# power_inputs.net
KiCad netlist of a schematic drawn in EAGLE
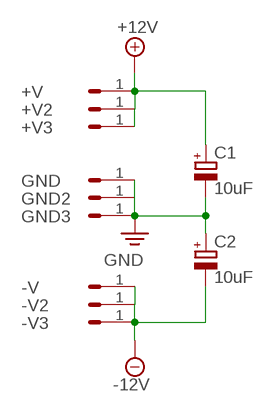
[diagram p0: schematic, sheet 1]

(export (version "E")
  (design (tool "Eeschema 10.0.6"))
  (components
    (comp (ref "+V")
      (value "HEADER/MALE/01")
      (footprint "eagle-import:HEADER_MALE_01")
      (fields (field (name "SPICEPREFIX") "X"))
      (libsource (lib "eagle-import") (part "HEADER/MALE/01"))
    )
    (comp (ref "+V2")
      (value "HEADER/MALE/01")
      (footprint "eagle-import:HEADER_MALE_01")
      (fields (field (name "SPICEPREFIX") "X"))
      (libsource (lib "eagle-import") (part "HEADER/MALE/01"))
    )
    (comp (ref "+V3")
      (value "HEADER/MALE/01")
      (footprint "eagle-import:HEADER_MALE_01")
      (fields (field (name "SPICEPREFIX") "X"))
      (libsource (lib "eagle-import") (part "HEADER/MALE/01"))
    )
    (comp (ref "-V")
      (value "HEADER/MALE/01")
      (footprint "eagle-import:HEADER_MALE_01")
      (fields (field (name "SPICEPREFIX") "X"))
      (libsource (lib "eagle-import") (part "HEADER/MALE/01"))
    )
    (comp (ref "-V2")
      (value "HEADER/MALE/01")
      (footprint "eagle-import:HEADER_MALE_01")
      (fields (field (name "SPICEPREFIX") "X"))
      (libsource (lib "eagle-import") (part "HEADER/MALE/01"))
    )
    (comp (ref "-V3")
      (value "HEADER/MALE/01")
      (footprint "eagle-import:HEADER_MALE_01")
      (fields (field (name "SPICEPREFIX") "X"))
      (libsource (lib "eagle-import") (part "HEADER/MALE/01"))
    )
    (comp (ref "C1")
      (value "10uF")
      (footprint "eagle-import:E2,5-6")
      (fields (field (name "SPICEPREFIX") "C"))
      (libsource (lib "eagle-import") (part "CAPACITOR/POLARIZEDE2.5-6"))
    )
    (comp (ref "C2")
      (value "10uF")
      (footprint "eagle-import:E2,5-6")
      (fields (field (name "SPICEPREFIX") "C"))
      (libsource (lib "eagle-import") (part "CAPACITOR/POLARIZEDE2.5-6"))
    )
    (comp (ref "GND")
      (value "HEADER/MALE/01")
      (footprint "eagle-import:HEADER_MALE_01")
      (fields (field (name "SPICEPREFIX") "X"))
      (libsource (lib "eagle-import") (part "HEADER/MALE/01"))
    )
    (comp (ref "GND2")
      (value "HEADER/MALE/01")
      (footprint "eagle-import:HEADER_MALE_01")
      (fields (field (name "SPICEPREFIX") "X"))
      (libsource (lib "eagle-import") (part "HEADER/MALE/01"))
    )
    (comp (ref "GND3")
      (value "HEADER/MALE/01")
      (footprint "eagle-import:HEADER_MALE_01")
      (fields (field (name "SPICEPREFIX") "X"))
      (libsource (lib "eagle-import") (part "HEADER/MALE/01"))
    )
  )
  (nets
    (net (code "1") (name "+12V") (class "Default")
      (node (ref "+V") (pin "1") (pinfunction "3_1") (pintype "passive"))
      (node (ref "+V2") (pin "1") (pinfunction "3_1") (pintype "passive"))
      (node (ref "+V3") (pin "1") (pinfunction "3_1") (pintype "passive"))
      (node (ref "C1") (pin "+") (pinfunction "+_+") (pintype "passive"))
    )
    (net (code "2") (name "-12V") (class "Default")
      (node (ref "-V") (pin "1") (pinfunction "3_1") (pintype "passive"))
      (node (ref "-V2") (pin "1") (pinfunction "3_1") (pintype "passive"))
      (node (ref "-V3") (pin "1") (pinfunction "3_1") (pintype "passive"))
      (node (ref "C2") (pin "-") (pinfunction "-_-") (pintype "passive"))
    )
    (net (code "3") (name "GND") (class "Default")
      (node (ref "C1") (pin "-") (pinfunction "-_-") (pintype "passive"))
      (node (ref "C2") (pin "+") (pinfunction "+_+") (pintype "passive"))
      (node (ref "GND") (pin "1") (pinfunction "3_1") (pintype "passive"))
      (node (ref "GND2") (pin "1") (pinfunction "3_1") (pintype "passive"))
      (node (ref "GND3") (pin "1") (pinfunction "3_1") (pintype "passive"))
    )
  )
)
